# SCH_d_00_ex_04.net
KiCad netlist of a schematic drawn in EasyEDA
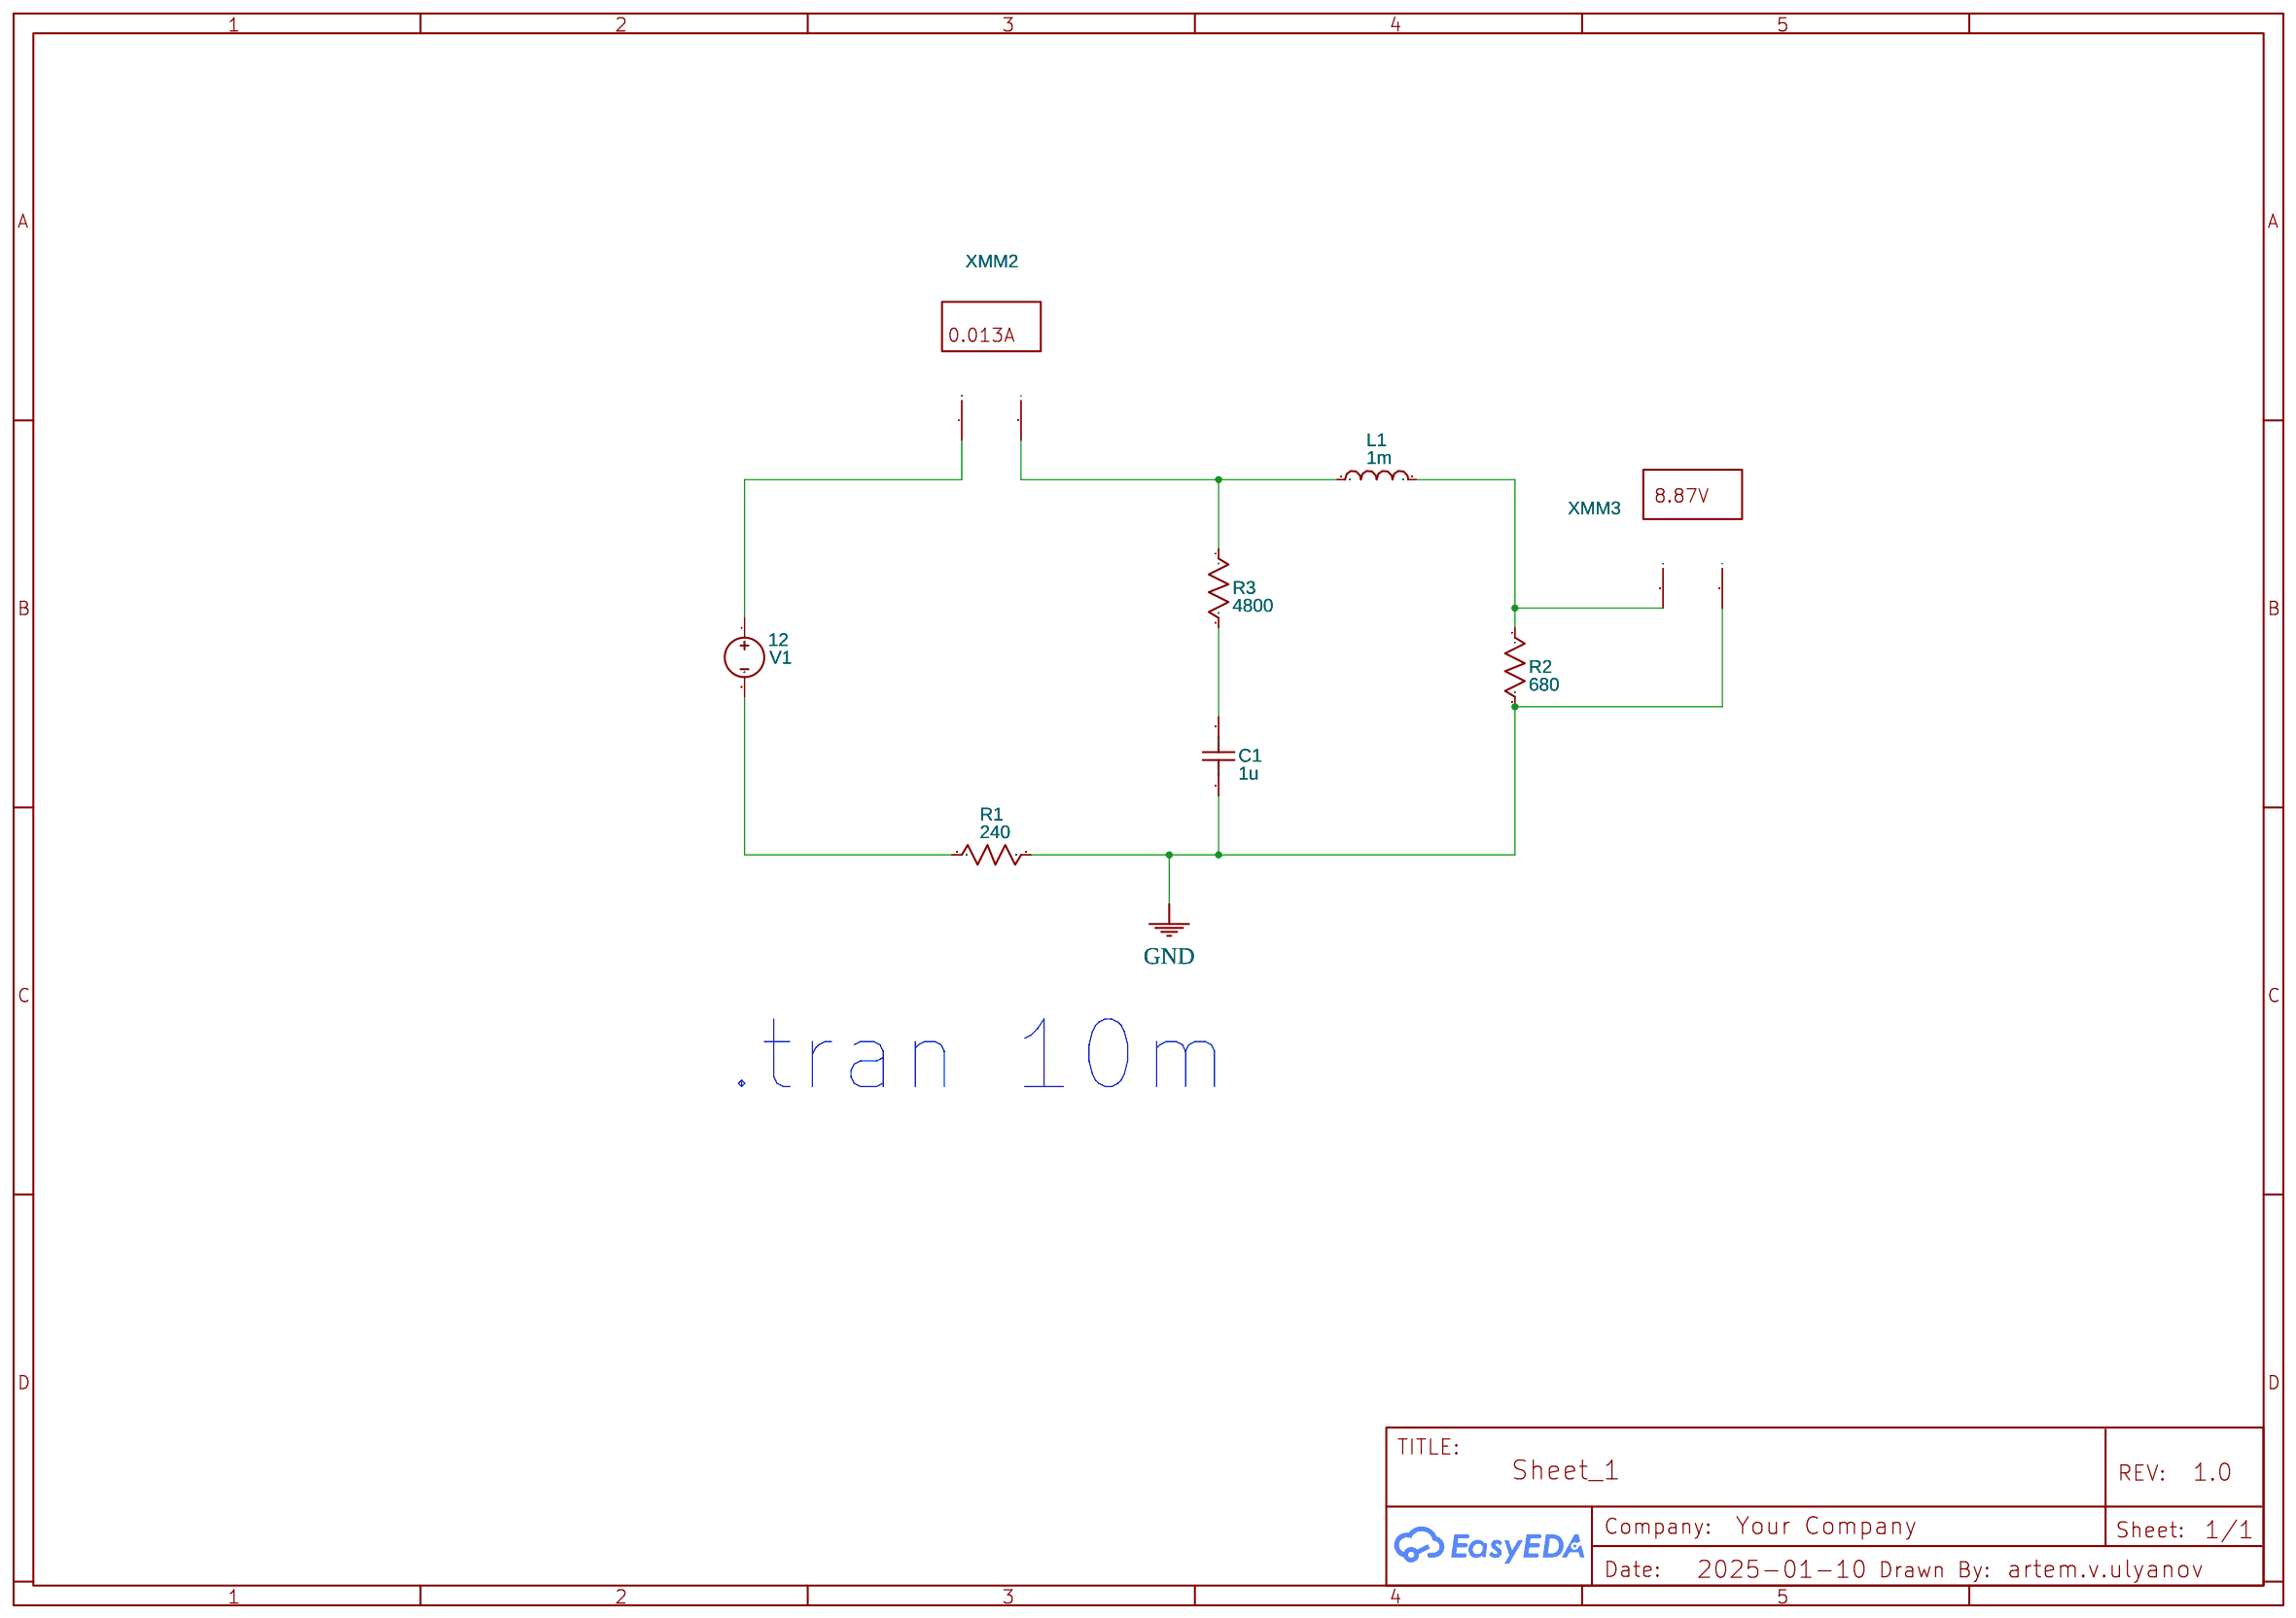
[diagram p0: schematic sheet]

(export (version "E")
  (design (tool "Eeschema 10.0.6"))
  (components
    (comp (ref "C1") (value "1u") (libsource (lib "") (part "Capacitor_US")))
    (comp (ref "L1") (value "1m") (libsource (lib "") (part "Inductor")))
    (comp (ref "R1") (value "240") (libsource (lib "") (part "Resistor_US_1")))
    (comp (ref "R2") (value "680") (libsource (lib "") (part "Resistor_US")))
    (comp (ref "R3") (value "4800") (libsource (lib "") (part "Resistor_US")))
    (comp (ref "V1") (value "12") (libsource (lib "") (part "VDC")))
    (comp (ref "XMM2") (value "Multimeter") (libsource (lib "") (part "MULTIMETER")))
    (comp (ref "XMM3") (value "Multimeter") (libsource (lib "") (part "MULTIMETER_1")))
  )
  (nets
    (net (code "1") (name "GND") (class "Default")
      (node (ref "C1") (pin "1") (pinfunction "1_1") (pintype "unspecified"))
      (node (ref "R1") (pin "2") (pinfunction "2_2") (pintype "unspecified"))
      (node (ref "R2") (pin "2") (pinfunction "2_2") (pintype "unspecified"))
      (node (ref "XMM3") (pin "2") (pinfunction "I_2") (pintype "unspecified"))
    )
    (net (code "2") (name "Net-(C1-Pad2)") (class "Default")
      (node (ref "C1") (pin "2") (pinfunction "2_2") (pintype "unspecified"))
      (node (ref "R3") (pin "2") (pinfunction "2_2") (pintype "unspecified"))
    )
    (net (code "3") (name "Net-(R1-Pad1)") (class "Default")
      (node (ref "R1") (pin "1") (pinfunction "1_1") (pintype "unspecified"))
      (node (ref "V1") (pin "2") (pinfunction "2_2") (pintype "unspecified"))
    )
    (net (code "4") (name "Net-(XMM2-+)") (class "Default")
      (node (ref "V1") (pin "1") (pinfunction "1_1") (pintype "unspecified"))
      (node (ref "XMM2") (pin "1") (pinfunction "+_1") (pintype "unspecified"))
    )
    (net (code "5") (name "Net-(XMM2-I)") (class "Default")
      (node (ref "L1") (pin "1") (pinfunction "1_1") (pintype "unspecified"))
      (node (ref "R3") (pin "1") (pinfunction "1_1") (pintype "unspecified"))
      (node (ref "XMM2") (pin "2") (pinfunction "I_2") (pintype "unspecified"))
    )
    (net (code "6") (name "Net-(XMM3-+)") (class "Default")
      (node (ref "L1") (pin "2") (pinfunction "2_2") (pintype "unspecified"))
      (node (ref "R2") (pin "1") (pinfunction "1_1") (pintype "unspecified"))
      (node (ref "XMM3") (pin "1") (pinfunction "+_1") (pintype "unspecified"))
    )
  )
)
